# Street_Fighter_v1_4.net
KiCad netlist of a schematic drawn in EAGLE
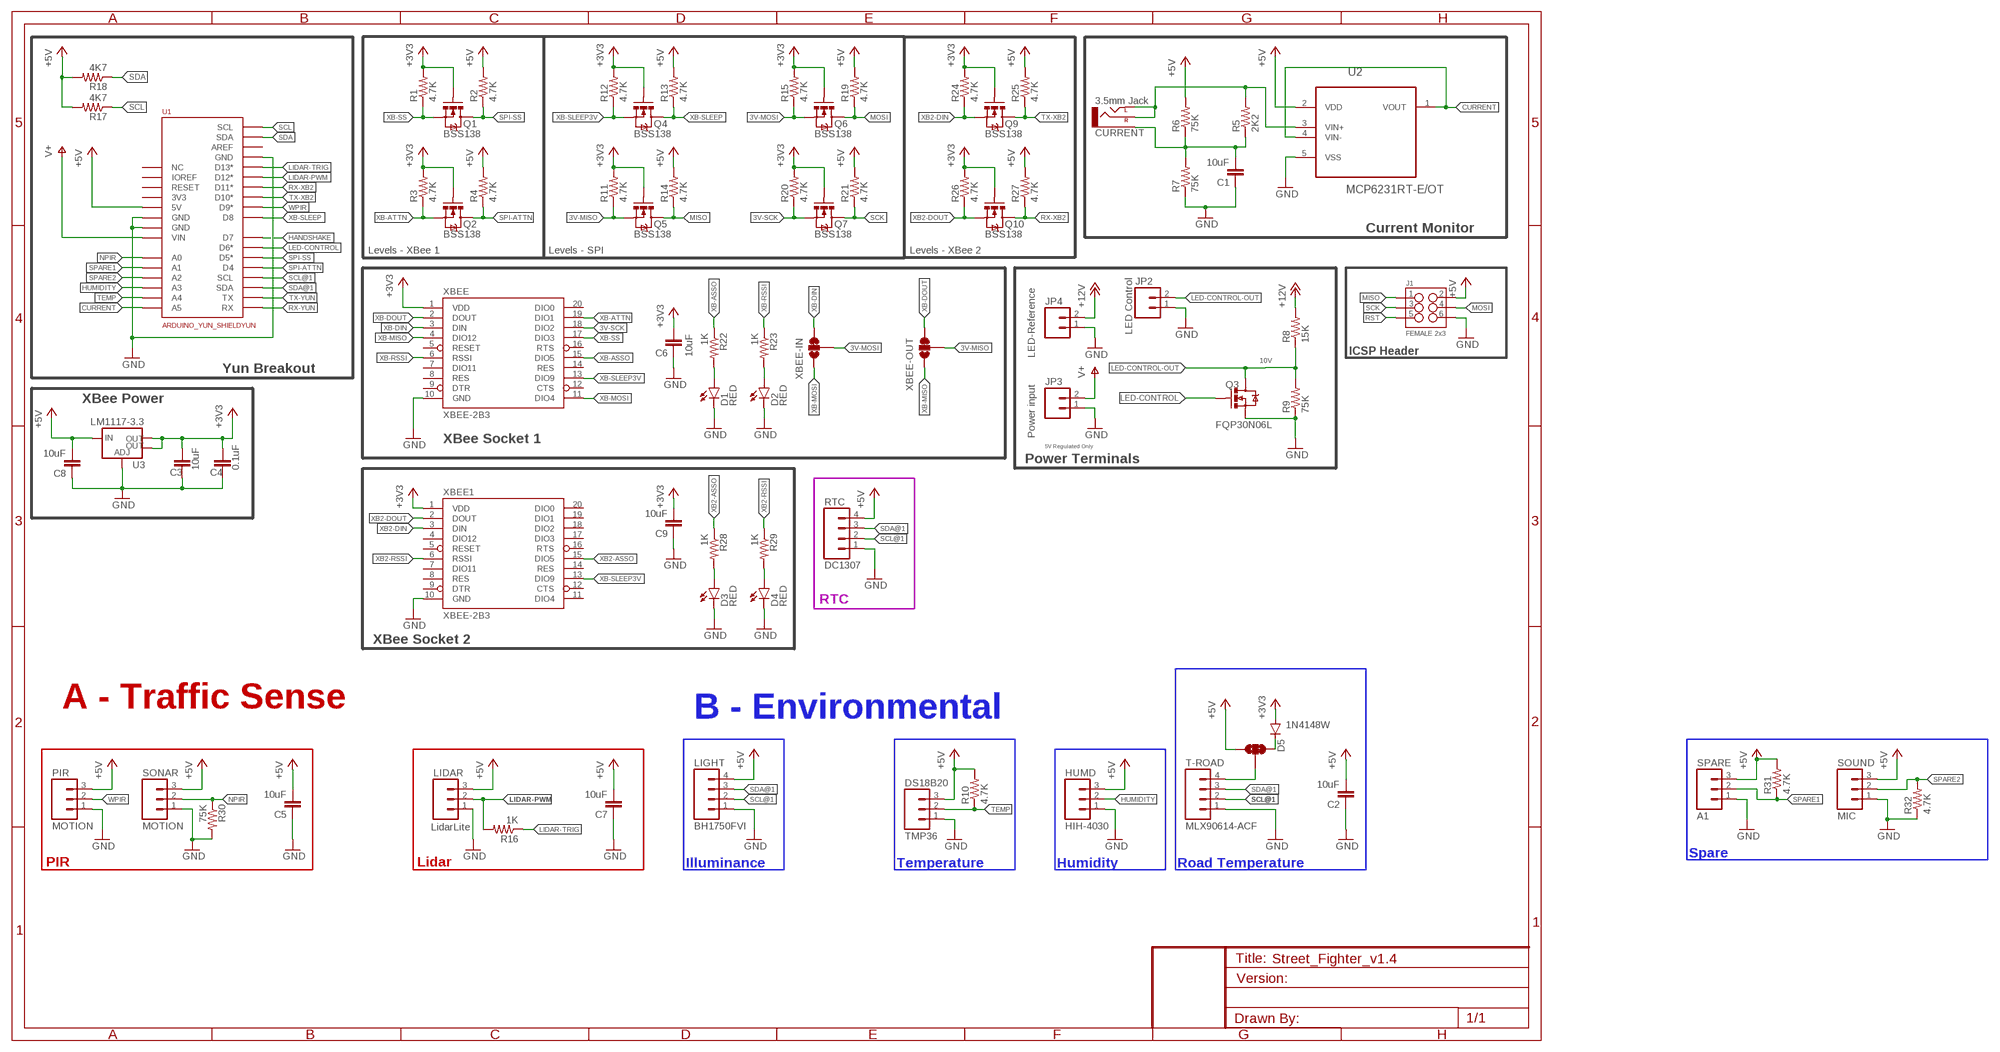
[diagram p0: schematic, sheet 1]

(export (version "E")
  (design (tool "Eeschema 10.0.6"))
  (components
    (comp (ref "C1")
      (value "10uF")
      (footprint "eagle-import:1206")
      (libsource (lib "eagle-import") (part "10UF-6.3V-20%(1206)"))
    )
    (comp (ref "C2")
      (value "10uF")
      (footprint "eagle-import:1206")
      (libsource (lib "eagle-import") (part "10UF-6.3V-20%(1206)"))
    )
    (comp (ref "C3")
      (value "10uF")
      (footprint "eagle-import:1206")
      (libsource (lib "eagle-import") (part "10UF-6.3V-20%(1206)"))
    )
    (comp (ref "C4")
      (value "0.1uF")
      (footprint "eagle-import:1206")
      (libsource (lib "eagle-import") (part "10UF-6.3V-20%(1206)"))
    )
    (comp (ref "C5")
      (value "10uF")
      (footprint "eagle-import:1206")
      (libsource (lib "eagle-import") (part "10UF-6.3V-20%(1206)"))
    )
    (comp (ref "C6")
      (value "10uF")
      (footprint "eagle-import:1206")
      (libsource (lib "eagle-import") (part "10UF-6.3V-20%(1206)"))
    )
    (comp (ref "C7")
      (value "10uF")
      (footprint "eagle-import:1206")
      (libsource (lib "eagle-import") (part "10UF-6.3V-20%(1206)"))
    )
    (comp (ref "C8")
      (value "10uF")
      (footprint "eagle-import:1206")
      (libsource (lib "eagle-import") (part "10UF-6.3V-20%(1206)"))
    )
    (comp (ref "C9")
      (value "10uF")
      (footprint "eagle-import:1206")
      (libsource (lib "eagle-import") (part "10UF-6.3V-20%(1206)"))
    )
    (comp (ref "CURRENT")
      (value "3.5mm Jack")
      (footprint "eagle-import:AUDIO-JACK")
      (libsource (lib "eagle-import") (part "AUDIO-JACKPTH"))
    )
    (comp (ref "D1")
      (value "RED")
      (footprint "eagle-import:LED-1206")
      (libsource (lib "eagle-import") (part "LED-RED1206"))
    )
    (comp (ref "D2")
      (value "RED")
      (footprint "eagle-import:LED-1206")
      (libsource (lib "eagle-import") (part "LED-RED1206"))
    )
    (comp (ref "D3")
      (value "RED")
      (footprint "eagle-import:LED-1206")
      (libsource (lib "eagle-import") (part "LED-RED1206"))
    )
    (comp (ref "D4")
      (value "RED")
      (footprint "eagle-import:LED-1206")
      (libsource (lib "eagle-import") (part "LED-RED1206"))
    )
    (comp (ref "D5")
      (value "1N4148W")
      (footprint "eagle-import:SOD-123")
      (libsource (lib "eagle-import") (part "DIODESOD123"))
    )
    (comp (ref "DS18B20")
      (value "TMP36")
      (footprint "eagle-import:1X03")
      (libsource (lib "eagle-import") (part "M03PTH"))
    )
    (comp (ref "HUMD")
      (value "HIH-4030")
      (footprint "eagle-import:1X03")
      (libsource (lib "eagle-import") (part "M03PTH"))
    )
    (comp (ref "J1")
      (value "FEMALE 2x3")
      (footprint "eagle-import:2X3")
      (libsource (lib "eagle-import") (part "M03X2FEMALE"))
    )
    (comp (ref "JP2")
      (value "LED Control")
      (footprint "eagle-import:1X02_LONGPADS")
      (libsource (lib "eagle-import") (part "M02PTH3"))
    )
    (comp (ref "JP3")
      (value "Power input")
      (footprint "eagle-import:1X02_LONGPADS")
      (libsource (lib "eagle-import") (part "M02PTH3"))
    )
    (comp (ref "JP4")
      (value "LED-Reference")
      (footprint "eagle-import:1X02_LONGPADS")
      (libsource (lib "eagle-import") (part "M02PTH3"))
    )
    (comp (ref "LIDAR")
      (value "LidarLite")
      (footprint "eagle-import:1X03")
      (libsource (lib "eagle-import") (part "M03PTH"))
    )
    (comp (ref "LIGHT")
      (value "BH1750FVI")
      (footprint "eagle-import:1X04")
      (libsource (lib "eagle-import") (part "M04PTH"))
    )
    (comp (ref "PIR")
      (value "MOTION")
      (footprint "eagle-import:1X03")
      (libsource (lib "eagle-import") (part "M03PTH"))
    )
    (comp (ref "Q1")
      (value "BSS138")
      (footprint "eagle-import:SOT23")
      (libsource (lib "eagle-import") (part "MOSFET-NCHANNELBSS123LT1G"))
    )
    (comp (ref "Q2")
      (value "BSS138")
      (footprint "eagle-import:SOT23")
      (libsource (lib "eagle-import") (part "MOSFET-NCHANNELBSS123LT1G"))
    )
    (comp (ref "Q3")
      (value "FQP30N06L")
      (footprint "eagle-import:TO220V")
      (libsource (lib "eagle-import") (part "MOSFET-NCHANNELFQP30N06L"))
    )
    (comp (ref "Q4")
      (value "BSS138")
      (footprint "eagle-import:SOT23")
      (libsource (lib "eagle-import") (part "MOSFET-NCHANNELBSS123LT1G"))
    )
    (comp (ref "Q5")
      (value "BSS138")
      (footprint "eagle-import:SOT23")
      (libsource (lib "eagle-import") (part "MOSFET-NCHANNELBSS123LT1G"))
    )
    (comp (ref "Q6")
      (value "BSS138")
      (footprint "eagle-import:SOT23")
      (libsource (lib "eagle-import") (part "MOSFET-NCHANNELBSS123LT1G"))
    )
    (comp (ref "Q7")
      (value "BSS138")
      (footprint "eagle-import:SOT23")
      (libsource (lib "eagle-import") (part "MOSFET-NCHANNELBSS123LT1G"))
    )
    (comp (ref "Q9")
      (value "BSS138")
      (footprint "eagle-import:SOT23")
      (libsource (lib "eagle-import") (part "MOSFET-NCHANNELBSS123LT1G"))
    )
    (comp (ref "Q10")
      (value "BSS138")
      (footprint "eagle-import:SOT23")
      (libsource (lib "eagle-import") (part "MOSFET-NCHANNELBSS123LT1G"))
    )
    (comp (ref "R1")
      (value "4.7K")
      (footprint "eagle-import:1206")
      (libsource (lib "eagle-import") (part "RESISTOR1206"))
    )
    (comp (ref "R2")
      (value "4.7K")
      (footprint "eagle-import:1206")
      (libsource (lib "eagle-import") (part "RESISTOR1206"))
    )
    (comp (ref "R3")
      (value "4.7K")
      (footprint "eagle-import:1206")
      (libsource (lib "eagle-import") (part "RESISTOR1206"))
    )
    (comp (ref "R4")
      (value "4.7K")
      (footprint "eagle-import:1206")
      (libsource (lib "eagle-import") (part "RESISTOR1206"))
    )
    (comp (ref "R5")
      (value "2K2")
      (footprint "eagle-import:1206")
      (libsource (lib "eagle-import") (part "RESISTOR1206"))
    )
    (comp (ref "R6")
      (value "75K")
      (footprint "eagle-import:1206")
      (libsource (lib "eagle-import") (part "RESISTOR1206"))
    )
    (comp (ref "R7")
      (value "75K")
      (footprint "eagle-import:1206")
      (libsource (lib "eagle-import") (part "RESISTOR1206"))
    )
    (comp (ref "R8")
      (value "15K")
      (footprint "eagle-import:1206")
      (libsource (lib "eagle-import") (part "RESISTOR1206"))
    )
    (comp (ref "R9")
      (value "75K")
      (footprint "eagle-import:1206")
      (libsource (lib "eagle-import") (part "RESISTOR1206"))
    )
    (comp (ref "R10")
      (value "4.7K")
      (footprint "eagle-import:1206")
      (libsource (lib "eagle-import") (part "RESISTOR1206"))
    )
    (comp (ref "R11")
      (value "4.7K")
      (footprint "eagle-import:1206")
      (libsource (lib "eagle-import") (part "RESISTOR1206"))
    )
    (comp (ref "R12")
      (value "4.7K")
      (footprint "eagle-import:1206")
      (libsource (lib "eagle-import") (part "RESISTOR1206"))
    )
    (comp (ref "R13")
      (value "4.7K")
      (footprint "eagle-import:1206")
      (libsource (lib "eagle-import") (part "RESISTOR1206"))
    )
    (comp (ref "R14")
      (value "4.7K")
      (footprint "eagle-import:1206")
      (libsource (lib "eagle-import") (part "RESISTOR1206"))
    )
    (comp (ref "R15")
      (value "4.7K")
      (footprint "eagle-import:1206")
      (libsource (lib "eagle-import") (part "RESISTOR1206"))
    )
    (comp (ref "R16")
      (value "1K")
      (footprint "eagle-import:1206")
      (libsource (lib "eagle-import") (part "RESISTOR1206"))
    )
    (comp (ref "R17")
      (value "4K7")
      (footprint "eagle-import:1206")
      (libsource (lib "eagle-import") (part "RESISTOR1206"))
    )
    (comp (ref "R18")
      (value "4K7")
      (footprint "eagle-import:1206")
      (libsource (lib "eagle-import") (part "RESISTOR1206"))
    )
    (comp (ref "R19")
      (value "4.7K")
      (footprint "eagle-import:1206")
      (libsource (lib "eagle-import") (part "RESISTOR1206"))
    )
    (comp (ref "R20")
      (value "4.7K")
      (footprint "eagle-import:1206")
      (libsource (lib "eagle-import") (part "RESISTOR1206"))
    )
    (comp (ref "R21")
      (value "4.7K")
      (footprint "eagle-import:1206")
      (libsource (lib "eagle-import") (part "RESISTOR1206"))
    )
    (comp (ref "R22")
      (value "1K")
      (footprint "eagle-import:1206")
      (libsource (lib "eagle-import") (part "RESISTOR1206"))
    )
    (comp (ref "R23")
      (value "1K")
      (footprint "eagle-import:1206")
      (libsource (lib "eagle-import") (part "RESISTOR1206"))
    )
    (comp (ref "R24")
      (value "4.7K")
      (footprint "eagle-import:1206")
      (libsource (lib "eagle-import") (part "RESISTOR1206"))
    )
    (comp (ref "R25")
      (value "4.7K")
      (footprint "eagle-import:1206")
      (libsource (lib "eagle-import") (part "RESISTOR1206"))
    )
    (comp (ref "R26")
      (value "4.7K")
      (footprint "eagle-import:1206")
      (libsource (lib "eagle-import") (part "RESISTOR1206"))
    )
    (comp (ref "R27")
      (value "4.7K")
      (footprint "eagle-import:1206")
      (libsource (lib "eagle-import") (part "RESISTOR1206"))
    )
    (comp (ref "R28")
      (value "1K")
      (footprint "eagle-import:1206")
      (libsource (lib "eagle-import") (part "RESISTOR1206"))
    )
    (comp (ref "R29")
      (value "1K")
      (footprint "eagle-import:1206")
      (libsource (lib "eagle-import") (part "RESISTOR1206"))
    )
    (comp (ref "R30")
      (value "75K")
      (footprint "eagle-import:1206")
      (libsource (lib "eagle-import") (part "RESISTOR1206"))
    )
    (comp (ref "R31")
      (value "4.7K")
      (footprint "eagle-import:1206")
      (libsource (lib "eagle-import") (part "RESISTOR1206"))
    )
    (comp (ref "R32")
      (value "4.7K")
      (footprint "eagle-import:1206")
      (libsource (lib "eagle-import") (part "RESISTOR1206"))
    )
    (comp (ref "RTC")
      (value "DC1307")
      (footprint "eagle-import:1X04")
      (libsource (lib "eagle-import") (part "M04PTH"))
    )
    (comp (ref "SONAR")
      (value "MOTION")
      (footprint "eagle-import:1X03")
      (libsource (lib "eagle-import") (part "M03PTH"))
    )
    (comp (ref "SOUND")
      (value "MIC")
      (footprint "eagle-import:1X03")
      (libsource (lib "eagle-import") (part "M03PTH"))
    )
    (comp (ref "SPARE")
      (value "A1")
      (footprint "eagle-import:1X03")
      (libsource (lib "eagle-import") (part "M03PTH"))
    )
    (comp (ref "T-ROAD")
      (value "MLX90614-ACF")
      (footprint "eagle-import:1X04")
      (libsource (lib "eagle-import") (part "M04PTH"))
    )
    (comp (ref "U1")
      (value "ARDUINO_YUN_SHIELDYUN")
      (footprint "eagle-import:DUEMILANOVE_VIAS")
      (libsource (lib "eagle-import") (part "ARDUINO_YUN_SHIELDYUN"))
    )
    (comp (ref "U2")
      (value "MCP6231RT-E/OT")
      (footprint "eagle-import:SOT95P270X145-5N")
      (libsource (lib "eagle-import") (part "MCP6231RT-E/OT"))
    )
    (comp (ref "U3")
      (value "LM1117-3.3")
      (footprint "eagle-import:SOT223")
      (libsource (lib "eagle-import") (part "V_REG_LM1117SOT223"))
    )
    (comp (ref "XBEE")
      (value "XBEE-2B3")
      (footprint "eagle-import:XBEE-SMD")
      (libsource (lib "eagle-import") (part "XBEE-2B3"))
    )
    (comp (ref "XBEE-IN")
      (value "JUMPER-PAD-3-2OF3_NC_BY_TRACE_SMALL")
      (footprint "eagle-import:PAD-JUMPER-3-2OF3_NC_BY_TRACE_YES_SILK_FULL_BOX")
      (libsource (lib "eagle-import") (part "JUMPER-PAD-3-2OF3_NC_BY_TRACE_SMALL"))
    )
    (comp (ref "XBEE-OUT")
      (value "JUMPER-PAD-3-2OF3_NC_BY_TRACE_SMALL")
      (footprint "eagle-import:PAD-JUMPER-3-2OF3_NC_BY_TRACE_YES_SILK_FULL_BOX")
      (libsource (lib "eagle-import") (part "JUMPER-PAD-3-2OF3_NC_BY_TRACE_SMALL"))
    )
    (comp (ref "XBEE-OUT1")
      (value "JUMPER-PAD-3-2OF3_NC_BY_TRACE_SMALL")
      (footprint "eagle-import:PAD-JUMPER-3-2OF3_NC_BY_TRACE_YES_SILK_FULL_BOX")
      (libsource (lib "eagle-import") (part "JUMPER-PAD-3-2OF3_NC_BY_TRACE_SMALL"))
    )
    (comp (ref "XBEE1")
      (value "XBEE-2B3")
      (footprint "eagle-import:XBEE-SMD")
      (libsource (lib "eagle-import") (part "XBEE-2B3"))
    )
  )
  (nets
    (net (code "1") (name "+3V3") (class "Default")
      (node (ref "C3") (pin "2") (pinfunction "2_2") (pintype "passive"))
      (node (ref "C4") (pin "2") (pinfunction "2_2") (pintype "passive"))
      (node (ref "C6") (pin "2") (pinfunction "2_2") (pintype "passive"))
      (node (ref "C9") (pin "2") (pinfunction "2_2") (pintype "passive"))
      (node (ref "D5") (pin "A") (pinfunction "A_A") (pintype "passive"))
      (node (ref "Q1") (pin "1") (pinfunction "G_1") (pintype "passive"))
      (node (ref "Q10") (pin "1") (pinfunction "G_1") (pintype "passive"))
      (node (ref "Q2") (pin "1") (pinfunction "G_1") (pintype "passive"))
      (node (ref "Q4") (pin "1") (pinfunction "G_1") (pintype "passive"))
      (node (ref "Q5") (pin "1") (pinfunction "G_1") (pintype "passive"))
      (node (ref "Q6") (pin "1") (pinfunction "G_1") (pintype "passive"))
      (node (ref "Q7") (pin "1") (pinfunction "G_1") (pintype "passive"))
      (node (ref "Q9") (pin "1") (pinfunction "G_1") (pintype "passive"))
      (node (ref "R1") (pin "2") (pinfunction "2_2") (pintype "passive"))
      (node (ref "R11") (pin "2") (pinfunction "2_2") (pintype "passive"))
      (node (ref "R12") (pin "2") (pinfunction "2_2") (pintype "passive"))
      (node (ref "R15") (pin "2") (pinfunction "2_2") (pintype "passive"))
      (node (ref "R20") (pin "2") (pinfunction "2_2") (pintype "passive"))
      (node (ref "R24") (pin "2") (pinfunction "2_2") (pintype "passive"))
      (node (ref "R26") (pin "2") (pinfunction "2_2") (pintype "passive"))
      (node (ref "R3") (pin "2") (pinfunction "2_2") (pintype "passive"))
      (node (ref "U3") (pin "2") (pinfunction "OUT_2") (pintype "output"))
      (node (ref "U3") (pin "4") (pinfunction "OUT_4") (pintype "output"))
      (node (ref "XBEE") (pin "1") (pinfunction "VDD_1") (pintype "power_in"))
      (node (ref "XBEE1") (pin "1") (pinfunction "VDD_1") (pintype "power_in"))
    )
    (net (code "2") (name "+5V") (class "Default")
      (node (ref "C2") (pin "2") (pinfunction "2_2") (pintype "passive"))
      (node (ref "C5") (pin "2") (pinfunction "2_2") (pintype "passive"))
      (node (ref "C7") (pin "2") (pinfunction "2_2") (pintype "passive"))
      (node (ref "C8") (pin "2") (pinfunction "2_2") (pintype "passive"))
      (node (ref "DS18B20") (pin "3") (pinfunction "3_3") (pintype "passive"))
      (node (ref "HUMD") (pin "3") (pinfunction "3_3") (pintype "passive"))
      (node (ref "J1") (pin "2") (pinfunction "2_2") (pintype "bidirectional"))
      (node (ref "LIDAR") (pin "3") (pinfunction "3_3") (pintype "passive"))
      (node (ref "LIGHT") (pin "4") (pinfunction "4_4") (pintype "passive"))
      (node (ref "PIR") (pin "3") (pinfunction "3_3") (pintype "passive"))
      (node (ref "R10") (pin "2") (pinfunction "2_2") (pintype "passive"))
      (node (ref "R13") (pin "2") (pinfunction "2_2") (pintype "passive"))
      (node (ref "R14") (pin "2") (pinfunction "2_2") (pintype "passive"))
      (node (ref "R17") (pin "2") (pinfunction "2_2") (pintype "passive"))
      (node (ref "R18") (pin "2") (pinfunction "2_2") (pintype "passive"))
      (node (ref "R19") (pin "2") (pinfunction "2_2") (pintype "passive"))
      (node (ref "R2") (pin "2") (pinfunction "2_2") (pintype "passive"))
      (node (ref "R21") (pin "2") (pinfunction "2_2") (pintype "passive"))
      (node (ref "R25") (pin "2") (pinfunction "2_2") (pintype "passive"))
      (node (ref "R27") (pin "2") (pinfunction "2_2") (pintype "passive"))
      (node (ref "R31") (pin "2") (pinfunction "2_2") (pintype "passive"))
      (node (ref "R4") (pin "2") (pinfunction "2_2") (pintype "passive"))
      (node (ref "R6") (pin "2") (pinfunction "2_2") (pintype "passive"))
      (node (ref "RTC") (pin "4") (pinfunction "4_4") (pintype "passive"))
      (node (ref "SONAR") (pin "3") (pinfunction "3_3") (pintype "passive"))
      (node (ref "SOUND") (pin "3") (pinfunction "3_3") (pintype "passive"))
      (node (ref "SPARE") (pin "3") (pinfunction "3_3") (pintype "passive"))
      (node (ref "U1") (pin "5V") (pinfunction "5V_5V") (pintype "power_in"))
      (node (ref "U2") (pin "2") (pinfunction "VDD_2") (pintype "power_in"))
      (node (ref "U3") (pin "3") (pinfunction "IN_3") (pintype "input"))
      (node (ref "XBEE-OUT1") (pin "1") (pinfunction "1_1") (pintype "passive"))
    )
    (net (code "3") (name "+12V") (class "Default")
      (node (ref "JP4") (pin "2") (pinfunction "2_2") (pintype "passive"))
      (node (ref "R8") (pin "2") (pinfunction "2_2") (pintype "passive"))
    )
    (net (code "4") (name "/3V3") (class "Default")
      (node (ref "U1") (pin "3V3") (pinfunction "3V3_3V3") (pintype "power_in"))
    )
    (net (code "5") (name "3V-MISO") (class "Default")
      (node (ref "Q5") (pin "2") (pinfunction "S_2") (pintype "passive"))
      (node (ref "R11") (pin "1") (pinfunction "1_1") (pintype "passive"))
      (node (ref "XBEE-OUT") (pin "2") (pinfunction "2_2") (pintype "passive"))
    )
    (net (code "6") (name "3V-MOSI") (class "Default")
      (node (ref "Q6") (pin "2") (pinfunction "S_2") (pintype "passive"))
      (node (ref "R15") (pin "1") (pinfunction "1_1") (pintype "passive"))
      (node (ref "XBEE-IN") (pin "2") (pinfunction "2_2") (pintype "passive"))
    )
    (net (code "7") (name "3V-SCK") (class "Default")
      (node (ref "Q7") (pin "2") (pinfunction "S_2") (pintype "passive"))
      (node (ref "R20") (pin "1") (pinfunction "1_1") (pintype "passive"))
      (node (ref "XBEE") (pin "18") (pinfunction "DIO2_18") (pintype "bidirectional"))
    )
    (net (code "8") (name "CURRENT") (class "Default")
      (node (ref "U1") (pin "A5") (pinfunction "A5_A5") (pintype "bidirectional"))
      (node (ref "U2") (pin "1") (pinfunction "VOUT_1") (pintype "output"))
      (node (ref "U2") (pin "4") (pinfunction "VIN-_4") (pintype "input"))
    )
    (net (code "9") (name "GND") (class "Default")
      (node (ref "C1") (pin "1") (pinfunction "1_1") (pintype "passive"))
      (node (ref "C2") (pin "1") (pinfunction "1_1") (pintype "passive"))
      (node (ref "C3") (pin "1") (pinfunction "1_1") (pintype "passive"))
      (node (ref "C4") (pin "1") (pinfunction "1_1") (pintype "passive"))
      (node (ref "C5") (pin "1") (pinfunction "1_1") (pintype "passive"))
      (node (ref "C6") (pin "1") (pinfunction "1_1") (pintype "passive"))
      (node (ref "C7") (pin "1") (pinfunction "1_1") (pintype "passive"))
      (node (ref "C8") (pin "1") (pinfunction "1_1") (pintype "passive"))
      (node (ref "C9") (pin "1") (pinfunction "1_1") (pintype "passive"))
      (node (ref "D1") (pin "C") (pinfunction "C_C") (pintype "passive"))
      (node (ref "D2") (pin "C") (pinfunction "C_C") (pintype "passive"))
      (node (ref "D3") (pin "C") (pinfunction "C_C") (pintype "passive"))
      (node (ref "D4") (pin "C") (pinfunction "C_C") (pintype "passive"))
      (node (ref "DS18B20") (pin "1") (pinfunction "1_1") (pintype "passive"))
      (node (ref "HUMD") (pin "1") (pinfunction "1_1") (pintype "passive"))
      (node (ref "J1") (pin "6") (pinfunction "6_6") (pintype "bidirectional"))
      (node (ref "JP2") (pin "1") (pinfunction "1_1") (pintype "passive"))
      (node (ref "JP3") (pin "1") (pinfunction "1_1") (pintype "passive"))
      (node (ref "JP4") (pin "1") (pinfunction "1_1") (pintype "passive"))
      (node (ref "LIDAR") (pin "1") (pinfunction "1_1") (pintype "passive"))
      (node (ref "LIGHT") (pin "1") (pinfunction "1_1") (pintype "passive"))
      (node (ref "PIR") (pin "1") (pinfunction "1_1") (pintype "passive"))
      (node (ref "Q3") (pin "3") (pinfunction "S_3") (pintype "passive"))
      (node (ref "R30") (pin "2") (pinfunction "2_2") (pintype "passive"))
      (node (ref "R32") (pin "1") (pinfunction "1_1") (pintype "passive"))
      (node (ref "R7") (pin "1") (pinfunction "1_1") (pintype "passive"))
      (node (ref "R9") (pin "1") (pinfunction "1_1") (pintype "passive"))
      (node (ref "RTC") (pin "1") (pinfunction "1_1") (pintype "passive"))
      (node (ref "SONAR") (pin "1") (pinfunction "1_1") (pintype "passive"))
      (node (ref "SOUND") (pin "1") (pinfunction "1_1") (pintype "passive"))
      (node (ref "SPARE") (pin "1") (pinfunction "1_1") (pintype "passive"))
      (node (ref "T-ROAD") (pin "1") (pinfunction "1_1") (pintype "passive"))
      (node (ref "U1") (pin "GND") (pinfunction "GND_GND") (pintype "power_in"))
      (node (ref "U1") (pin "GND@0") (pinfunction "GND_GND@0") (pintype "power_in"))
      (node (ref "U1") (pin "GND@1") (pinfunction "GND_GND@1") (pintype "power_in"))
      (node (ref "U2") (pin "5") (pinfunction "VSS_5") (pintype "passive"))
      (node (ref "U3") (pin "1") (pinfunction "ADJ_1") (pintype "input"))
      (node (ref "XBEE") (pin "10") (pinfunction "GND_10") (pintype "power_in"))
      (node (ref "XBEE1") (pin "10") (pinfunction "GND_10") (pintype "power_in"))
    )
    (net (code "10") (name "HANDSHAKE") (class "Default")
      (node (ref "U1") (pin "7") (pinfunction "D7_7") (pintype "bidirectional"))
    )
    (net (code "11") (name "HUMIDITY") (class "Default")
      (node (ref "HUMD") (pin "2") (pinfunction "2_2") (pintype "passive"))
      (node (ref "U1") (pin "A3") (pinfunction "A3_A3") (pintype "bidirectional"))
    )
    (net (code "12") (name "LED-CONTROL") (class "Default")
      (node (ref "Q3") (pin "1") (pinfunction "G_1") (pintype "passive"))
      (node (ref "U1") (pin "6") (pinfunction "D6*_6") (pintype "bidirectional"))
    )
    (net (code "13") (name "LED-CONTROL-OUT") (class "Default")
      (node (ref "JP2") (pin "2") (pinfunction "2_2") (pintype "passive"))
      (node (ref "Q3") (pin "2") (pinfunction "D_2") (pintype "passive"))
      (node (ref "R8") (pin "1") (pinfunction "1_1") (pintype "passive"))
      (node (ref "R9") (pin "2") (pinfunction "2_2") (pintype "passive"))
    )
    (net (code "14") (name "LIDAR-PWM") (class "Default")
      (node (ref "LIDAR") (pin "2") (pinfunction "2_2") (pintype "passive"))
      (node (ref "R16") (pin "2") (pinfunction "2_2") (pintype "passive"))
      (node (ref "U1") (pin "12") (pinfunction "D12*_12") (pintype "bidirectional"))
    )
    (net (code "15") (name "LIDAR-TRIG") (class "Default")
      (node (ref "R16") (pin "1") (pinfunction "1_1") (pintype "passive"))
      (node (ref "U1") (pin "13") (pinfunction "D13*_13") (pintype "bidirectional"))
    )
    (net (code "16") (name "MISO") (class "Default")
      (node (ref "J1") (pin "1") (pinfunction "1_1") (pintype "bidirectional"))
      (node (ref "Q5") (pin "3") (pinfunction "D_3") (pintype "passive"))
      (node (ref "R14") (pin "1") (pinfunction "1_1") (pintype "passive"))
    )
    (net (code "17") (name "MOSI") (class "Default")
      (node (ref "J1") (pin "4") (pinfunction "4_4") (pintype "bidirectional"))
      (node (ref "Q6") (pin "3") (pinfunction "D_3") (pintype "passive"))
      (node (ref "R19") (pin "1") (pinfunction "1_1") (pintype "passive"))
    )
    (net (code "18") (name "NPIR") (class "Default")
      (node (ref "R30") (pin "1") (pinfunction "1_1") (pintype "passive"))
      (node (ref "SONAR") (pin "2") (pinfunction "2_2") (pintype "passive"))
      (node (ref "U1") (pin "A0") (pinfunction "A0_A0") (pintype "bidirectional"))
    )
    (net (code "19") (name "Net-(C1-Pad2)") (class "Default")
      (node (ref "C1") (pin "2") (pinfunction "2_2") (pintype "passive"))
      (node (ref "CURRENT") (pin "SLEEVE") (pinfunction "SLEEVE_SLEEVE") (pintype "bidirectional"))
      (node (ref "R5") (pin "1") (pinfunction "1_1") (pintype "passive"))
      (node (ref "R6") (pin "1") (pinfunction "1_1") (pintype "passive"))
      (node (ref "R7") (pin "2") (pinfunction "2_2") (pintype "passive"))
    )
    (net (code "20") (name "Net-(CURRENT-LEFT)") (class "Default")
      (node (ref "CURRENT") (pin "RING") (pinfunction "RIGHT_RING") (pintype "bidirectional"))
      (node (ref "CURRENT") (pin "TIP") (pinfunction "LEFT_TIP") (pintype "bidirectional"))
      (node (ref "R5") (pin "2") (pinfunction "2_2") (pintype "passive"))
      (node (ref "U2") (pin "3") (pinfunction "VIN+_3") (pintype "input"))
    )
    (net (code "21") (name "Net-(D1-PadA)") (class "Default")
      (node (ref "D1") (pin "A") (pinfunction "A_A") (pintype "passive"))
      (node (ref "R22") (pin "2") (pinfunction "2_2") (pintype "passive"))
    )
    (net (code "22") (name "Net-(D2-PadA)") (class "Default")
      (node (ref "D2") (pin "A") (pinfunction "A_A") (pintype "passive"))
      (node (ref "R23") (pin "2") (pinfunction "2_2") (pintype "passive"))
    )
    (net (code "23") (name "Net-(D3-PadA)") (class "Default")
      (node (ref "D3") (pin "A") (pinfunction "A_A") (pintype "passive"))
      (node (ref "R28") (pin "2") (pinfunction "2_2") (pintype "passive"))
    )
    (net (code "24") (name "Net-(D4-PadA)") (class "Default")
      (node (ref "D4") (pin "A") (pinfunction "A_A") (pintype "passive"))
      (node (ref "R29") (pin "2") (pinfunction "2_2") (pintype "passive"))
    )
    (net (code "25") (name "Net-(D5-PadC)") (class "Default")
      (node (ref "D5") (pin "C") (pinfunction "C_C") (pintype "passive"))
      (node (ref "XBEE-OUT1") (pin "3") (pinfunction "3_3") (pintype "passive"))
    )
    (net (code "26") (name "Net-(T-ROAD-Pad4)") (class "Default")
      (node (ref "T-ROAD") (pin "4") (pinfunction "4_4") (pintype "passive"))
      (node (ref "XBEE-OUT1") (pin "2") (pinfunction "2_2") (pintype "passive"))
    )
    (net (code "27") (name "RST") (class "Default")
      (node (ref "J1") (pin "5") (pinfunction "5_5") (pintype "bidirectional"))
    )
    (net (code "28") (name "RX-XB2") (class "Default")
      (node (ref "Q10") (pin "3") (pinfunction "D_3") (pintype "passive"))
      (node (ref "R27") (pin "1") (pinfunction "1_1") (pintype "passive"))
      (node (ref "U1") (pin "11") (pinfunction "D11*_11") (pintype "bidirectional"))
    )
    (net (code "29") (name "RX-YUN") (class "Default")
      (node (ref "U1") (pin "0") (pinfunction "RX_0") (pintype "bidirectional"))
    )
    (net (code "30") (name "SCK") (class "Default")
      (node (ref "J1") (pin "3") (pinfunction "3_3") (pintype "bidirectional"))
      (node (ref "Q7") (pin "3") (pinfunction "D_3") (pintype "passive"))
      (node (ref "R21") (pin "1") (pinfunction "1_1") (pintype "passive"))
    )
    (net (code "31") (name "SCL") (class "Default")
      (node (ref "R17") (pin "1") (pinfunction "1_1") (pintype "passive"))
      (node (ref "U1") (pin "3@1") (pinfunction "SCL_3@1") (pintype "bidirectional"))
    )
    (net (code "32") (name "SCL@1") (class "Default")
      (node (ref "LIGHT") (pin "2") (pinfunction "2_2") (pintype "passive"))
      (node (ref "RTC") (pin "2") (pinfunction "2_2") (pintype "passive"))
      (node (ref "T-ROAD") (pin "2") (pinfunction "2_2") (pintype "passive"))
      (node (ref "U1") (pin "3") (pinfunction "SCL_3") (pintype "bidirectional"))
    )
    (net (code "33") (name "SDA") (class "Default")
      (node (ref "R18") (pin "1") (pinfunction "1_1") (pintype "passive"))
      (node (ref "U1") (pin "2@1") (pinfunction "SDA_2@1") (pintype "bidirectional"))
    )
    (net (code "34") (name "SDA@1") (class "Default")
      (node (ref "LIGHT") (pin "3") (pinfunction "3_3") (pintype "passive"))
      (node (ref "RTC") (pin "3") (pinfunction "3_3") (pintype "passive"))
      (node (ref "T-ROAD") (pin "3") (pinfunction "3_3") (pintype "passive"))
      (node (ref "U1") (pin "2") (pinfunction "SDA_2") (pintype "bidirectional"))
    )
    (net (code "35") (name "SPARE1") (class "Default")
      (node (ref "R31") (pin "1") (pinfunction "1_1") (pintype "passive"))
      (node (ref "SPARE") (pin "2") (pinfunction "2_2") (pintype "passive"))
      (node (ref "U1") (pin "A1") (pinfunction "A1_A1") (pintype "bidirectional"))
    )
    (net (code "36") (name "SPARE2") (class "Default")
      (node (ref "R32") (pin "2") (pinfunction "2_2") (pintype "passive"))
      (node (ref "SOUND") (pin "2") (pinfunction "2_2") (pintype "passive"))
      (node (ref "U1") (pin "A2") (pinfunction "A2_A2") (pintype "bidirectional"))
    )
    (net (code "37") (name "SPI-ATTN") (class "Default")
      (node (ref "Q2") (pin "3") (pinfunction "D_3") (pintype "passive"))
      (node (ref "R4") (pin "1") (pinfunction "1_1") (pintype "passive"))
      (node (ref "U1") (pin "D4") (pinfunction "D4_D4") (pintype "bidirectional"))
    )
    (net (code "38") (name "SPI-SS") (class "Default")
      (node (ref "Q1") (pin "3") (pinfunction "D_3") (pintype "passive"))
      (node (ref "R2") (pin "1") (pinfunction "1_1") (pintype "passive"))
      (node (ref "U1") (pin "5") (pinfunction "D5*_5") (pintype "bidirectional"))
    )
    (net (code "39") (name "TEMP") (class "Default")
      (node (ref "DS18B20") (pin "2") (pinfunction "2_2") (pintype "passive"))
      (node (ref "R10") (pin "1") (pinfunction "1_1") (pintype "passive"))
      (node (ref "U1") (pin "A4") (pinfunction "A4_A4") (pintype "bidirectional"))
    )
    (net (code "40") (name "TX-XB2") (class "Default")
      (node (ref "Q9") (pin "3") (pinfunction "D_3") (pintype "passive"))
      (node (ref "R25") (pin "1") (pinfunction "1_1") (pintype "passive"))
      (node (ref "U1") (pin "10") (pinfunction "D10*_10") (pintype "bidirectional"))
    )
    (net (code "41") (name "TX-YUN") (class "Default")
      (node (ref "U1") (pin "1") (pinfunction "TX_1") (pintype "bidirectional"))
    )
    (net (code "42") (name "V+") (class "Default")
      (node (ref "JP3") (pin "2") (pinfunction "2_2") (pintype "passive"))
      (node (ref "U1") (pin "VIN") (pinfunction "VIN_VIN") (pintype "power_in"))
    )
    (net (code "43") (name "WPIR") (class "Default")
      (node (ref "PIR") (pin "2") (pinfunction "2_2") (pintype "passive"))
      (node (ref "U1") (pin "9") (pinfunction "D9*_9") (pintype "bidirectional"))
    )
    (net (code "44") (name "XB-ASSO") (class "Default")
      (node (ref "R22") (pin "1") (pinfunction "1_1") (pintype "passive"))
      (node (ref "XBEE") (pin "15") (pinfunction "DIO5_15") (pintype "bidirectional"))
    )
    (net (code "45") (name "XB-ATTN") (class "Default")
      (node (ref "Q2") (pin "2") (pinfunction "S_2") (pintype "passive"))
      (node (ref "R3") (pin "1") (pinfunction "1_1") (pintype "passive"))
      (node (ref "XBEE") (pin "19") (pinfunction "DIO1_19") (pintype "bidirectional"))
    )
    (net (code "46") (name "XB-DIN") (class "Default")
      (node (ref "XBEE") (pin "3") (pinfunction "DIN_3") (pintype "input"))
      (node (ref "XBEE-IN") (pin "3") (pinfunction "3_3") (pintype "passive"))
    )
    (net (code "47") (name "XB-DOUT") (class "Default")
      (node (ref "XBEE") (pin "2") (pinfunction "DOUT_2") (pintype "output"))
      (node (ref "XBEE-OUT") (pin "3") (pinfunction "3_3") (pintype "passive"))
    )
    (net (code "48") (name "XB-MISO") (class "Default")
      (node (ref "XBEE") (pin "4") (pinfunction "DIO12_4") (pintype "bidirectional"))
      (node (ref "XBEE-OUT") (pin "1") (pinfunction "1_1") (pintype "passive"))
    )
    (net (code "49") (name "XB-MOSI") (class "Default")
      (node (ref "XBEE") (pin "11") (pinfunction "DIO4_11") (pintype "bidirectional"))
      (node (ref "XBEE-IN") (pin "1") (pinfunction "1_1") (pintype "passive"))
    )
    (net (code "50") (name "XB-RSSI") (class "Default")
      (node (ref "R23") (pin "1") (pinfunction "1_1") (pintype "passive"))
      (node (ref "XBEE") (pin "6") (pinfunction "RSSI_6") (pintype "bidirectional"))
    )
    (net (code "51") (name "XB-SLEEP") (class "Default")
      (node (ref "Q4") (pin "3") (pinfunction "D_3") (pintype "passive"))
      (node (ref "R13") (pin "1") (pinfunction "1_1") (pintype "passive"))
      (node (ref "U1") (pin "8") (pinfunction "D8_8") (pintype "bidirectional"))
    )
    (net (code "52") (name "XB-SLEEP3V") (class "Default")
      (node (ref "Q4") (pin "2") (pinfunction "S_2") (pintype "passive"))
      (node (ref "R12") (pin "1") (pinfunction "1_1") (pintype "passive"))
      (node (ref "XBEE") (pin "13") (pinfunction "DIO9_13") (pintype "bidirectional"))
      (node (ref "XBEE1") (pin "13") (pinfunction "DIO9_13") (pintype "bidirectional"))
    )
    (net (code "53") (name "XB-SS") (class "Default")
      (node (ref "Q1") (pin "2") (pinfunction "S_2") (pintype "passive"))
      (node (ref "R1") (pin "1") (pinfunction "1_1") (pintype "passive"))
      (node (ref "XBEE") (pin "17") (pinfunction "DIO3_17") (pintype "bidirectional"))
    )
    (net (code "54") (name "XB2-ASSO") (class "Default")
      (node (ref "R28") (pin "1") (pinfunction "1_1") (pintype "passive"))
      (node (ref "XBEE1") (pin "15") (pinfunction "DIO5_15") (pintype "bidirectional"))
    )
    (net (code "55") (name "XB2-DIN") (class "Default")
      (node (ref "Q9") (pin "2") (pinfunction "S_2") (pintype "passive"))
      (node (ref "R24") (pin "1") (pinfunction "1_1") (pintype "passive"))
      (node (ref "XBEE1") (pin "3") (pinfunction "DIN_3") (pintype "input"))
    )
    (net (code "56") (name "XB2-DOUT") (class "Default")
      (node (ref "Q10") (pin "2") (pinfunction "S_2") (pintype "passive"))
      (node (ref "R26") (pin "1") (pinfunction "1_1") (pintype "passive"))
      (node (ref "XBEE1") (pin "2") (pinfunction "DOUT_2") (pintype "output"))
    )
    (net (code "57") (name "XB2-RSSI") (class "Default")
      (node (ref "R29") (pin "1") (pinfunction "1_1") (pintype "passive"))
      (node (ref "XBEE1") (pin "6") (pinfunction "RSSI_6") (pintype "bidirectional"))
    )
    (net (code "58") (name "unconnected-(U1-PadAREF)") (class "Default")
      (node (ref "U1") (pin "AREF") (pinfunction "AREF_AREF") (pintype "bidirectional"))
    )
    (net (code "59") (name "unconnected-(U1-PadIOREF)") (class "Default")
      (node (ref "U1") (pin "IOREF") (pinfunction "IOREF_IOREF") (pintype "bidirectional"))
    )
    (net (code "60") (name "unconnected-(U1-PadNC)") (class "Default")
      (node (ref "U1") (pin "NC") (pinfunction "NC_NC") (pintype "no_connect"))
    )
    (net (code "61") (name "unconnected-(U1-PadRESET)") (class "Default")
      (node (ref "U1") (pin "RESET") (pinfunction "RESET_RESET") (pintype "bidirectional"))
    )
    (net (code "62") (name "unconnected-(XBEE-CTS-Pad12)") (class "Default")
      (node (ref "XBEE") (pin "12") (pinfunction "CTS_12") (pintype "output"))
    )
    (net (code "63") (name "unconnected-(XBEE-DIO0-Pad20)") (class "Default")
      (node (ref "XBEE") (pin "20") (pinfunction "DIO0_20") (pintype "bidirectional"))
    )
    (net (code "64") (name "unconnected-(XBEE-DIO11-Pad7)") (class "Default")
      (node (ref "XBEE") (pin "7") (pinfunction "DIO11_7") (pintype "bidirectional"))
    )
    (net (code "65") (name "unconnected-(XBEE-DTR-Pad9)") (class "Default")
      (node (ref "XBEE") (pin "9") (pinfunction "DTR_9") (pintype "bidirectional"))
    )
    (net (code "66") (name "unconnected-(XBEE-RES-Pad8)") (class "Default")
      (node (ref "XBEE") (pin "8") (pinfunction "RES_8") (pintype "bidirectional"))
    )
    (net (code "67") (name "unconnected-(XBEE-RES-Pad14)") (class "Default")
      (node (ref "XBEE") (pin "14") (pinfunction "RES_14") (pintype "bidirectional"))
    )
    (net (code "68") (name "unconnected-(XBEE-RESET-Pad5)") (class "Default")
      (node (ref "XBEE") (pin "5") (pinfunction "RESET_5") (pintype "input"))
    )
    (net (code "69") (name "unconnected-(XBEE-RTS-Pad16)") (class "Default")
      (node (ref "XBEE") (pin "16") (pinfunction "RTS_16") (pintype "input"))
    )
    (net (code "70") (name "unconnected-(XBEE1-CTS-Pad12)") (class "Default")
      (node (ref "XBEE1") (pin "12") (pinfunction "CTS_12") (pintype "output"))
    )
    (net (code "71") (name "unconnected-(XBEE1-DIO0-Pad20)") (class "Default")
      (node (ref "XBEE1") (pin "20") (pinfunction "DIO0_20") (pintype "bidirectional"))
    )
    (net (code "72") (name "unconnected-(XBEE1-DIO1-Pad19)") (class "Default")
      (node (ref "XBEE1") (pin "19") (pinfunction "DIO1_19") (pintype "bidirectional"))
    )
    (net (code "73") (name "unconnected-(XBEE1-DIO2-Pad18)") (class "Default")
      (node (ref "XBEE1") (pin "18") (pinfunction "DIO2_18") (pintype "bidirectional"))
    )
    (net (code "74") (name "unconnected-(XBEE1-DIO3-Pad17)") (class "Default")
      (node (ref "XBEE1") (pin "17") (pinfunction "DIO3_17") (pintype "bidirectional"))
    )
    (net (code "75") (name "unconnected-(XBEE1-DIO4-Pad11)") (class "Default")
      (node (ref "XBEE1") (pin "11") (pinfunction "DIO4_11") (pintype "bidirectional"))
    )
    (net (code "76") (name "unconnected-(XBEE1-DIO11-Pad7)") (class "Default")
      (node (ref "XBEE1") (pin "7") (pinfunction "DIO11_7") (pintype "bidirectional"))
    )
    (net (code "77") (name "unconnected-(XBEE1-DIO12-Pad4)") (class "Default")
      (node (ref "XBEE1") (pin "4") (pinfunction "DIO12_4") (pintype "bidirectional"))
    )
    (net (code "78") (name "unconnected-(XBEE1-DTR-Pad9)") (class "Default")
      (node (ref "XBEE1") (pin "9") (pinfunction "DTR_9") (pintype "bidirectional"))
    )
    (net (code "79") (name "unconnected-(XBEE1-RES-Pad8)") (class "Default")
      (node (ref "XBEE1") (pin "8") (pinfunction "RES_8") (pintype "bidirectional"))
    )
    (net (code "80") (name "unconnected-(XBEE1-RES-Pad14)") (class "Default")
      (node (ref "XBEE1") (pin "14") (pinfunction "RES_14") (pintype "bidirectional"))
    )
    (net (code "81") (name "unconnected-(XBEE1-RESET-Pad5)") (class "Default")
      (node (ref "XBEE1") (pin "5") (pinfunction "RESET_5") (pintype "input"))
    )
    (net (code "82") (name "unconnected-(XBEE1-RTS-Pad16)") (class "Default")
      (node (ref "XBEE1") (pin "16") (pinfunction "RTS_16") (pintype "input"))
    )
  )
)
